# 5_-POWER.net
KiCad netlist of a schematic drawn in Altium Designer
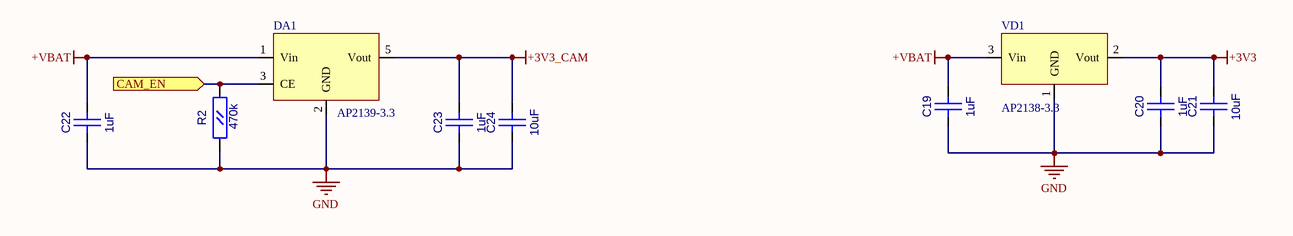
[diagram p0: [5]-POWER.SchDoc]

(export (version "E")
  (design (tool "Eeschema 10.0.6"))
  (components
    (comp (ref "C19")
      (value "1uF")
      (footprint "CC0603")
      (description "CC0603")
      (libsource (lib "gprs_modem_2") (part "CC0603"))
    )
    (comp (ref "C20")
      (value "1uF")
      (footprint "CC0603")
      (description "CC0603")
      (libsource (lib "gprs_modem_2") (part "CC0603"))
    )
    (comp (ref "C21")
      (value "10uF")
      (footprint "CC0805")
      (description "CC0805")
      (libsource (lib "gprs_modem_2") (part "CC0805"))
    )
    (comp (ref "C22")
      (value "1uF")
      (footprint "CC0603")
      (description "CC0603")
      (libsource (lib "gprs_modem_2") (part "CC0603"))
    )
    (comp (ref "C23")
      (value "1uF")
      (footprint "CC0603")
      (description "CC0603")
      (libsource (lib "gprs_modem_2") (part "CC0603"))
    )
    (comp (ref "C24")
      (value "10uF")
      (footprint "CC0805")
      (description "CC0805")
      (libsource (lib "gprs_modem_2") (part "CC0805"))
    )
    (comp (ref "DA1")
      (value "AP2139-3.3")
      (footprint "SOT23-5")
      (libsource (lib "fizik_lib") (part "AP2139"))
    )
    (comp (ref "R2")
      (value "470k")
      (footprint "RC0603")
      (description "RC0603")
      (libsource (lib "fizik_lib") (part "RC0603"))
    )
    (comp (ref "VD1")
      (value "AP2138-3.3")
      (footprint "SOT-23(123)")
      (libsource (lib "fizik_lib") (part "AP2138"))
    )
  )
  (nets
    (net (code "1") (name "+3V3") (class "Default")
      (node (ref "C20") (pin "2") (pinfunction "B_2") (pintype "passive"))
      (node (ref "C21") (pin "2") (pinfunction "B_2") (pintype "passive"))
      (node (ref "VD1") (pin "2") (pinfunction "Vout_2") (pintype "passive"))
    )
    (net (code "2") (name "+3V3_CAM") (class "Default")
      (node (ref "C23") (pin "2") (pinfunction "B_2") (pintype "passive"))
      (node (ref "C24") (pin "2") (pinfunction "B_2") (pintype "passive"))
      (node (ref "DA1") (pin "5") (pinfunction "Vout_5") (pintype "passive"))
    )
    (net (code "3") (name "+VBAT") (class "Default")
      (node (ref "C19") (pin "2") (pinfunction "B_2") (pintype "passive"))
      (node (ref "C22") (pin "2") (pinfunction "B_2") (pintype "passive"))
      (node (ref "DA1") (pin "1") (pinfunction "Vin_1") (pintype "passive"))
      (node (ref "VD1") (pin "3") (pinfunction "Vin_3") (pintype "passive"))
    )
    (net (code "4") (name "/CAM_EN") (class "Default")
      (node (ref "DA1") (pin "3") (pinfunction "CE_3") (pintype "passive"))
      (node (ref "R2") (pin "2") (pinfunction "B_2") (pintype "passive"))
    )
    (net (code "5") (name "GND") (class "Default")
      (node (ref "C19") (pin "1") (pinfunction "A_1") (pintype "passive"))
      (node (ref "C20") (pin "1") (pinfunction "A_1") (pintype "passive"))
      (node (ref "C21") (pin "1") (pinfunction "A_1") (pintype "passive"))
      (node (ref "C22") (pin "1") (pinfunction "A_1") (pintype "passive"))
      (node (ref "C23") (pin "1") (pinfunction "A_1") (pintype "passive"))
      (node (ref "C24") (pin "1") (pinfunction "A_1") (pintype "passive"))
      (node (ref "DA1") (pin "2") (pinfunction "GND_2") (pintype "passive"))
      (node (ref "R2") (pin "1") (pinfunction "A_1") (pintype "passive"))
      (node (ref "VD1") (pin "1") (pinfunction "GND_1") (pintype "passive"))
    )
  )
)
